# S02-POWER.net
KiCad netlist of a schematic drawn in Altium Designer
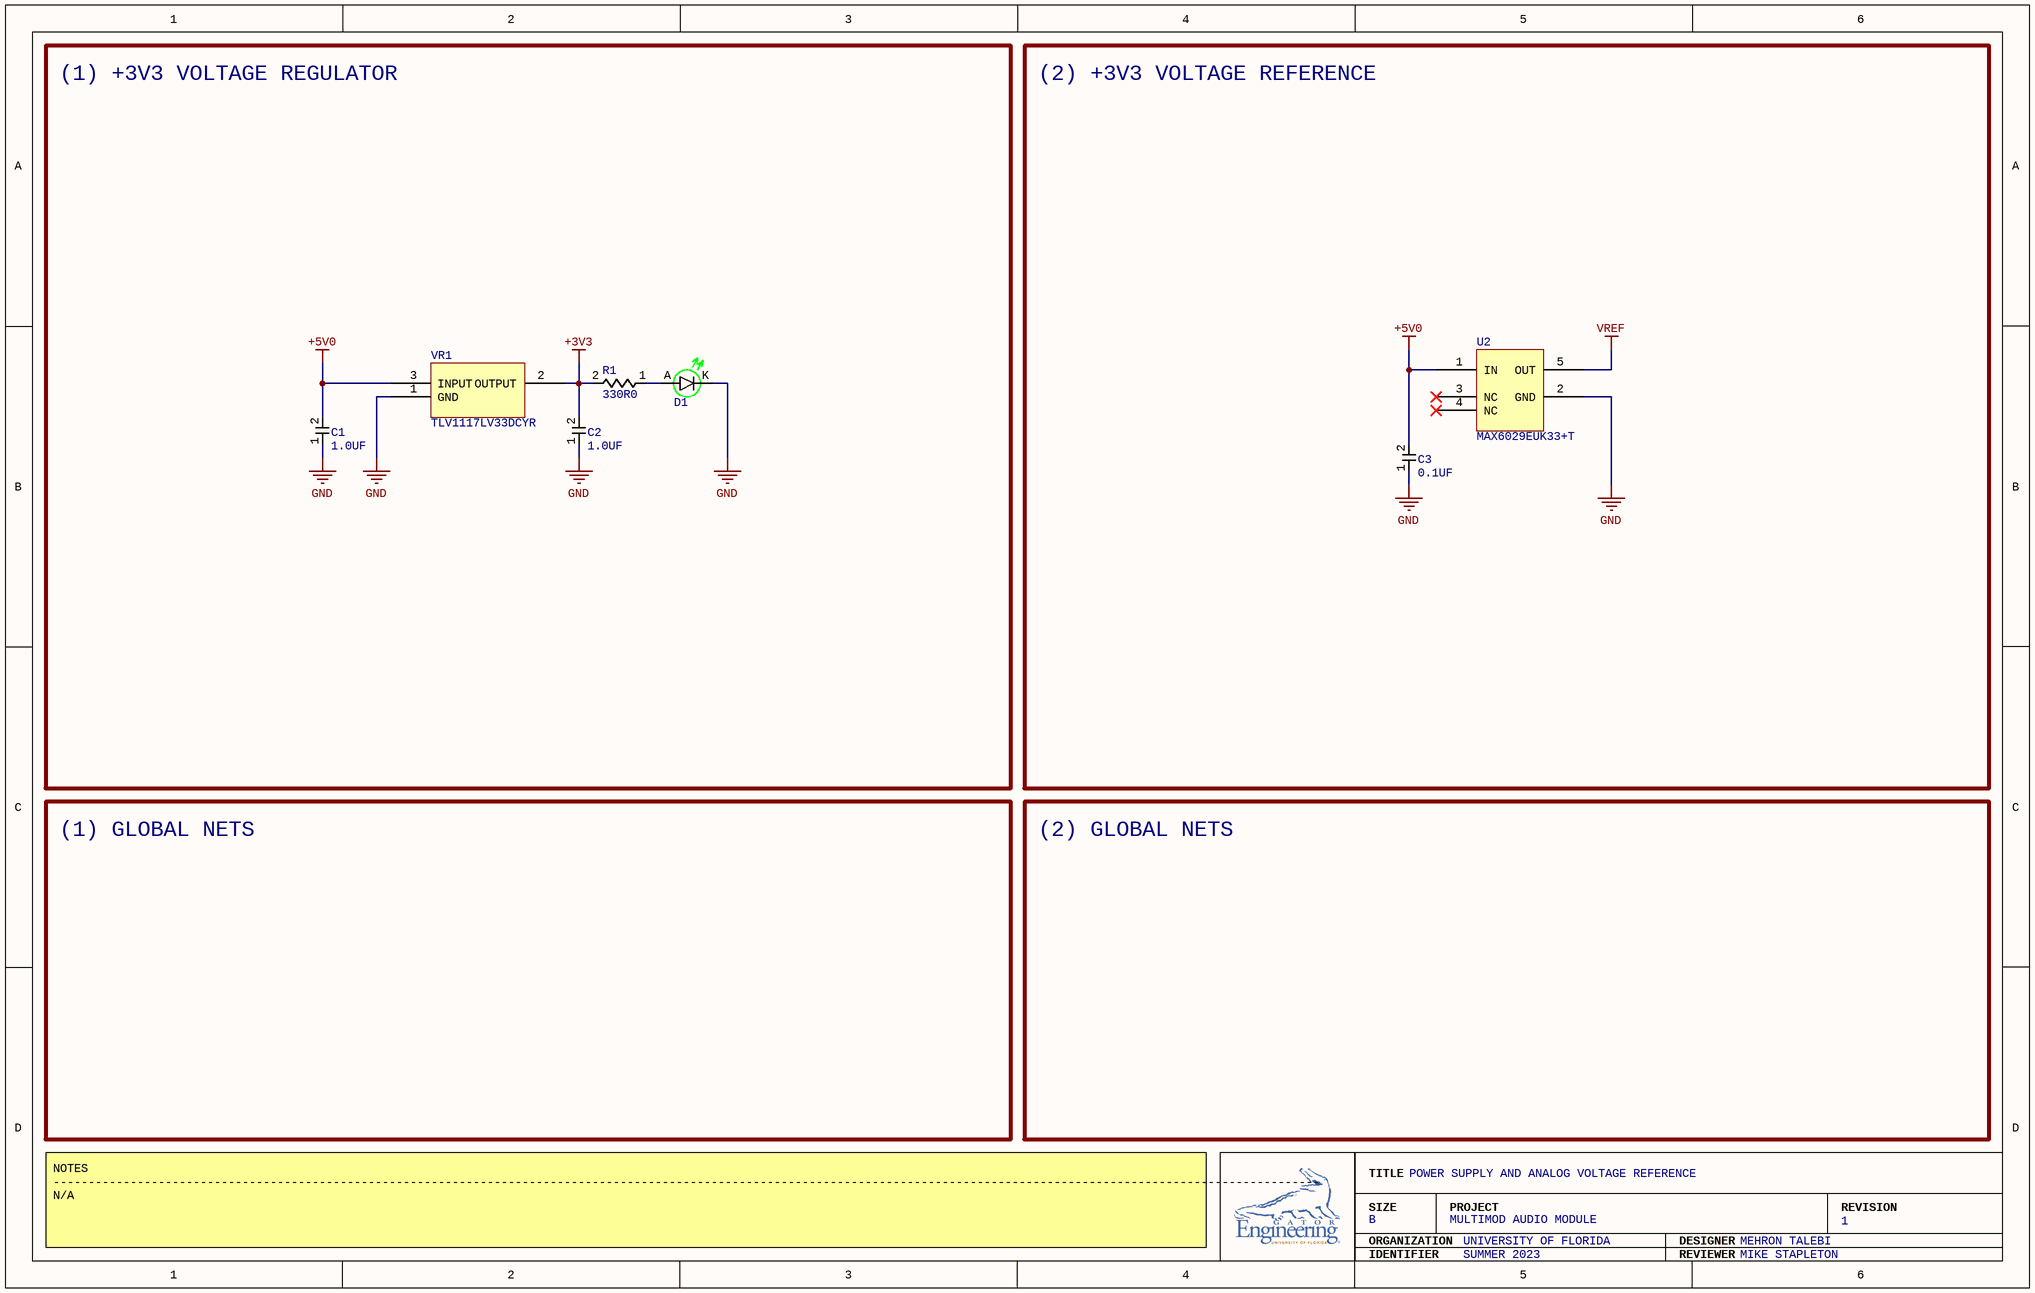
[diagram p0: S02-POWER.SchDoc]

(export (version "E")
  (design (tool "Eeschema 10.0.6"))
  (components
    (comp (ref "C1")
      (value "1.0UF")
      (footprint "CL21B105KAFNFNE")
      (description "CAP CER 1UF 25V X7R 0805")
      (fields (field (name "TOLERANCE") "±10%"))
      (libsource (lib "Master") (part "CL21B105KAFNFNE"))
    )
    (comp (ref "C2")
      (value "1.0UF")
      (footprint "CL21B105KAFNFNE")
      (description "CAP CER 1UF 25V X7R 0805")
      (fields (field (name "TOLERANCE") "±10%"))
      (libsource (lib "Master") (part "CL21B105KAFNFNE"))
    )
    (comp (ref "C3")
      (value "0.1UF")
      (footprint "CL21B104KACNNNC")
      (description "CAP CER 0.1UF 25V X7R 0805")
      (fields (field (name "TOLERANCE") "±10%"))
      (libsource (lib "Master") (part "CL21B104KACNNNC"))
    )
    (comp (ref "D1")
      (value "LTST-C171GKT")
      (footprint "LTST-C171GKT")
      (description "LED GREEN CLEAR CHIP SMD")
      (libsource (lib "Master") (part "LTST-C171GKT"))
    )
    (comp (ref "R1")
      (value "330R0")
      (footprint "RC0805FR-7W330RL")
      (description "RES 330 OHM 1% 1/4W 0805")
      (fields (field (name "TOLERANCE") "±1%"))
      (libsource (lib "Master") (part "RC0805FR-7W330RL"))
    )
    (comp (ref "U2")
      (value "MAX6029EUK33+T")
      (footprint "MAX6029EUK33+T")
      (description "IC VREF SERIES 0.15% SOT23-5")
      (fields (field (name "TOLERANCE") "±0.15%"))
      (libsource (lib "Master") (part "MAX6029EUK33+T"))
    )
    (comp (ref "VR1")
      (value "TLV1117LV33DCYR")
      (footprint "TLV1117LV33DCYR")
      (description "IC REG LINEAR 3.3V 1A SOT223-4")
      (libsource (lib "Master") (part "TLV1117LV33DCYR"))
    )
  )
  (nets
    (net (code "1") (name "+3V3") (class "Default")
      (node (ref "C2") (pin "2") (pinfunction "2_2") (pintype "passive"))
      (node (ref "R1") (pin "2") (pinfunction "2_2") (pintype "passive"))
      (node (ref "VR1") (pin "2") (pinfunction "OUTPUT_2") (pintype "passive"))
    )
    (net (code "2") (name "+5V0") (class "Default")
      (node (ref "C1") (pin "2") (pinfunction "2_2") (pintype "passive"))
      (node (ref "C3") (pin "2") (pinfunction "2_2") (pintype "passive"))
      (node (ref "U2") (pin "1") (pinfunction "IN_1") (pintype "passive"))
      (node (ref "VR1") (pin "3") (pinfunction "INPUT_3") (pintype "passive"))
    )
    (net (code "3") (name "GND") (class "Default")
      (node (ref "C1") (pin "1") (pinfunction "1_1") (pintype "passive"))
      (node (ref "C2") (pin "1") (pinfunction "1_1") (pintype "passive"))
      (node (ref "C3") (pin "1") (pinfunction "1_1") (pintype "passive"))
      (node (ref "D1") (pin "K") (pinfunction "K_K") (pintype "passive"))
      (node (ref "U2") (pin "2") (pinfunction "GND_2") (pintype "passive"))
      (node (ref "VR1") (pin "1") (pinfunction "GND_1") (pintype "passive"))
    )
    (net (code "4") (name "Net-(D1-PadA)") (class "Default")
      (node (ref "D1") (pin "A") (pinfunction "A_A") (pintype "passive"))
      (node (ref "R1") (pin "1") (pinfunction "1_1") (pintype "passive"))
    )
    (net (code "5") (name "VREF") (class "Default")
      (node (ref "U2") (pin "5") (pinfunction "OUT_5") (pintype "passive"))
    )
    (net (code "6") (name "unconnected-(U2-NC-Pad3)") (class "Default")
      (node (ref "U2") (pin "3") (pinfunction "NC_3") (pintype "passive+no_connect"))
    )
    (net (code "7") (name "unconnected-(U2-NC-Pad4)") (class "Default")
      (node (ref "U2") (pin "4") (pinfunction "NC_4") (pintype "passive+no_connect"))
    )
  )
)
